# 10-Power.net
KiCad netlist of a schematic drawn in Altium Designer
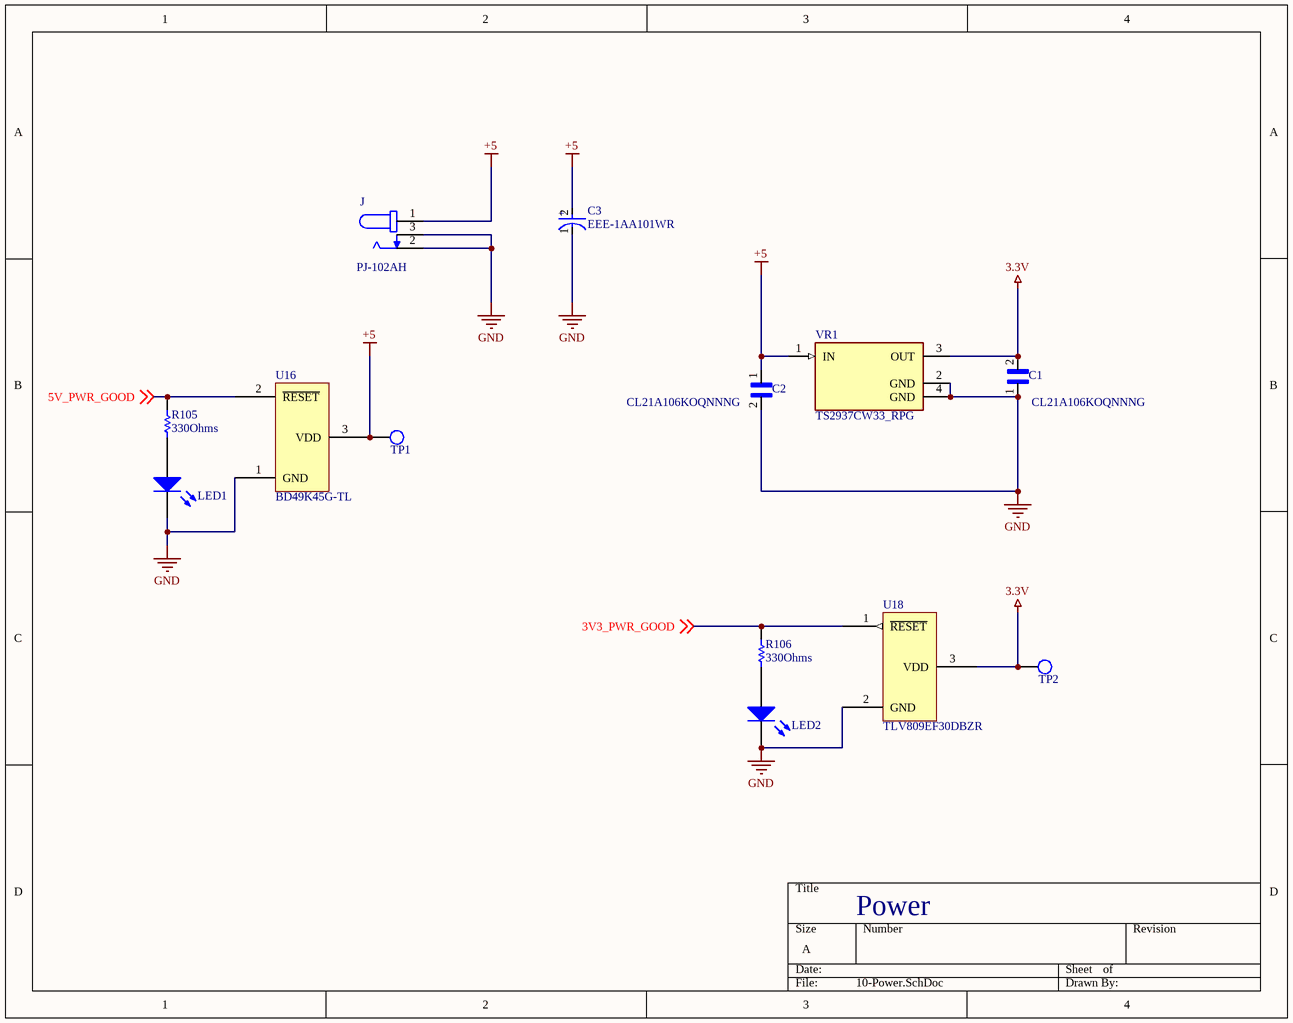
[diagram p0: 10-Power.SchDoc]

(export (version "E")
  (design (tool "Eeschema 10.0.6"))
  (components
    (comp (ref "C1")
      (value "CL21A106KOQNNNG")
      (footprint "CAPC2012X140N")
      (description "10ÂµF Â±10% 16V Ceramic Capacitor X5R 0805 _2012 Metric_")
      (fields
        (field (name "MF") "Samsung Electro-Mechanics")
        (field (name "DIGI-KEY_PART_NUMBER") "1276-6455-1-ND")
      )
      (libsource (lib "base-board") (part "CL21A106KOQNNNG"))
    )
    (comp (ref "C2")
      (value "CL21A106KOQNNNG")
      (footprint "CAPC2012X140N")
      (description "10ÂµF Â±10% 16V Ceramic Capacitor X5R 0805 _2012 Metric_")
      (fields
        (field (name "MF") "Samsung Electro-Mechanics")
        (field (name "DIGI-KEY_PART_NUMBER") "1276-6455-1-ND")
      )
      (libsource (lib "") (part "CL21A106KOQNNNG_1"))
    )
    (comp (ref "C3")
      (value "EEE-1AA101WR")
      (footprint "FP-SC-MFG")
      (description "CAP ALUM 100UF 20% 10V SMD")
      (fields (field (name "TOLERANCE") "20%"))
      (libsource (lib "Altium Content Vault") (part "a00bbbee19879c290e62620ae7e47b1"))
    )
    (comp (ref "J")
      (value "PJ-102AH")
      (footprint "CUI_PJ-102AH")
      (description "2.0 x 6.5 mm, 5.0 A, Horizontal, Through Hole, Tapered Pins, Dc Power Jack Connector")
      (fields (field (name "MF") "CUI Devices") (field (name "DIGI-KEY_PART_NUMBER") "CP-102AH-ND"))
      (libsource (lib "base-board") (part "PJ-102AH"))
    )
    (comp (ref "LED1")
      (value "150080RS75000")
      (footprint "0805_A")
      (description "SMD mono-color Chip LED, WL-SMCW, Red")
      (fields (field (name "MANUFACTURER") "Wuerth Elektronik"))
      (libsource (lib "Altium Content Vault") (part "WE-LED_K1A2-2"))
    )
    (comp (ref "LED2")
      (value "150080RS75000")
      (footprint "0805_A")
      (description "SMD mono-color Chip LED, WL-SMCW, Red")
      (fields (field (name "MANUFACTURER") "Wuerth Elektronik"))
      (libsource (lib "Altium Content Vault") (part "WE-LED_K1A2-2"))
    )
    (comp (ref "R105")
      (value "RC0805FR-07330RL")
      (footprint "RESC2013X60X35LL10T20")
      (description "Chip Resistor, 330 Ohm, +/- 1%, 125 mW, -55 to 155 degC, 0805 (2012 Metric), RoHS, Tape and Reel")
      (fields
        (field (name "MANUFACTURER") "Yageo")
        (field (name "TOLERANCE") "1%")
        (field (name "RESISTANCE") "330Ohms")
      )
      (libsource (lib "Altium Content Vault") (part "RES-2"))
    )
    (comp (ref "R106")
      (value "RC0805FR-07330RL")
      (footprint "RESC2013X60X35LL10T20")
      (description "Chip Resistor, 330 Ohm, +/- 1%, 125 mW, -55 to 155 degC, 0805 (2012 Metric), RoHS, Tape and Reel")
      (fields
        (field (name "MANUFACTURER") "Yageo")
        (field (name "TOLERANCE") "1%")
        (field (name "RESISTANCE") "330Ohms")
      )
      (libsource (lib "Altium Content Vault") (part "RES-2"))
    )
    (comp (ref "TP1")
      (value "TP_1206")
      (footprint "TP-SMC-1206")
      (description "Test Point SMD 1206")
      (fields
        (field (name "MANUFACTURER") "TE Connectivity (Tyco Electronics)")
        (field (name "MANUFACTURER PART NUMBER") "1625854-1")
      )
      (libsource (lib "base-board") (part "TP_1206"))
    )
    (comp (ref "TP2")
      (value "TP_1206")
      (footprint "TP-SMC-1206")
      (description "Test Point SMD 1206")
      (fields
        (field (name "MANUFACTURER") "TE Connectivity (Tyco Electronics)")
        (field (name "MANUFACTURER PART NUMBER") "1625854-1")
      )
      (libsource (lib "base-board") (part "TP_1206"))
    )
    (comp (ref "U16")
      (value "BD49K45G-TL")
      (footprint "SSOP3")
      (libsource (lib "base-board") (part "BD49K45G-TL"))
    )
    (comp (ref "U18")
      (value "TLV809EF30DBZR")
      (footprint "base-board:SOT95P237X112-3N")
      (libsource (lib "base-board") (part "TLV809EF30DBZR"))
    )
    (comp (ref "VR1")
      (value "TS2937CW33_RPG")
      (footprint "VREG_TS2937CW33_RPG")
      (libsource (lib "base-board") (part "TS2937CW33_RPG"))
    )
  )
  (nets
    (net (code "1") (name "+5") (class "Default")
      (node (ref "C2") (pin "1") (pinfunction "1_1") (pintype "passive"))
      (node (ref "C3") (pin "2") (pinfunction "A_2") (pintype "passive"))
      (node (ref "J") (pin "1") (pinfunction "1_1") (pintype "passive"))
      (node (ref "TP1") (pin "1") (pintype "passive"))
      (node (ref "U16") (pin "3") (pinfunction "VDD_3") (pintype "passive"))
      (node (ref "VR1") (pin "1") (pinfunction "IN_1") (pintype "input"))
    )
    (net (code "2") (name "3.3V") (class "Default")
      (node (ref "C1") (pin "2") (pinfunction "2_2") (pintype "passive"))
      (node (ref "TP2") (pin "1") (pintype "passive"))
      (node (ref "U18") (pin "3") (pinfunction "VDD_3") (pintype "passive"))
      (node (ref "VR1") (pin "3") (pinfunction "OUT_3") (pintype "power_in"))
    )
    (net (code "3") (name "3V3_PWR_GOOD") (class "Default")
      (node (ref "R106") (pin "2") (pinfunction "2_2") (pintype "passive"))
      (node (ref "U18") (pin "1") (pinfunction "~{RESET}_1") (pintype "output"))
    )
    (net (code "4") (name "5V_PWR_GOOD") (class "Default")
      (node (ref "R105") (pin "2") (pinfunction "2_2") (pintype "passive"))
      (node (ref "U16") (pin "2") (pinfunction "~{RESET}_2") (pintype "passive"))
    )
    (net (code "5") (name "GND") (class "Default")
      (node (ref "C1") (pin "1") (pinfunction "1_1") (pintype "passive"))
      (node (ref "C2") (pin "2") (pinfunction "2_2") (pintype "passive"))
      (node (ref "C3") (pin "1") (pinfunction "C_1") (pintype "passive"))
      (node (ref "J") (pin "2") (pinfunction "2_2") (pintype "passive"))
      (node (ref "J") (pin "3") (pinfunction "3_3") (pintype "passive"))
      (node (ref "LED1") (pin "1") (pinfunction "K_1") (pintype "passive"))
      (node (ref "LED2") (pin "1") (pinfunction "K_1") (pintype "passive"))
      (node (ref "U16") (pin "1") (pinfunction "GND_1") (pintype "passive"))
      (node (ref "U18") (pin "2") (pinfunction "GND_2") (pintype "passive"))
      (node (ref "VR1") (pin "2") (pinfunction "GND_2") (pintype "power_in"))
      (node (ref "VR1") (pin "4") (pinfunction "GND_4") (pintype "power_in"))
    )
    (net (code "6") (name "Net-(LED1-A)") (class "Default")
      (node (ref "LED1") (pin "2") (pinfunction "A_2") (pintype "passive"))
      (node (ref "R105") (pin "1") (pinfunction "1_1") (pintype "passive"))
    )
    (net (code "7") (name "Net-(LED2-A)") (class "Default")
      (node (ref "LED2") (pin "2") (pinfunction "A_2") (pintype "passive"))
      (node (ref "R106") (pin "1") (pinfunction "1_1") (pintype "passive"))
    )
  )
)
